# BW1092_Connector.net
KiCad netlist of a schematic drawn in Altium Designer
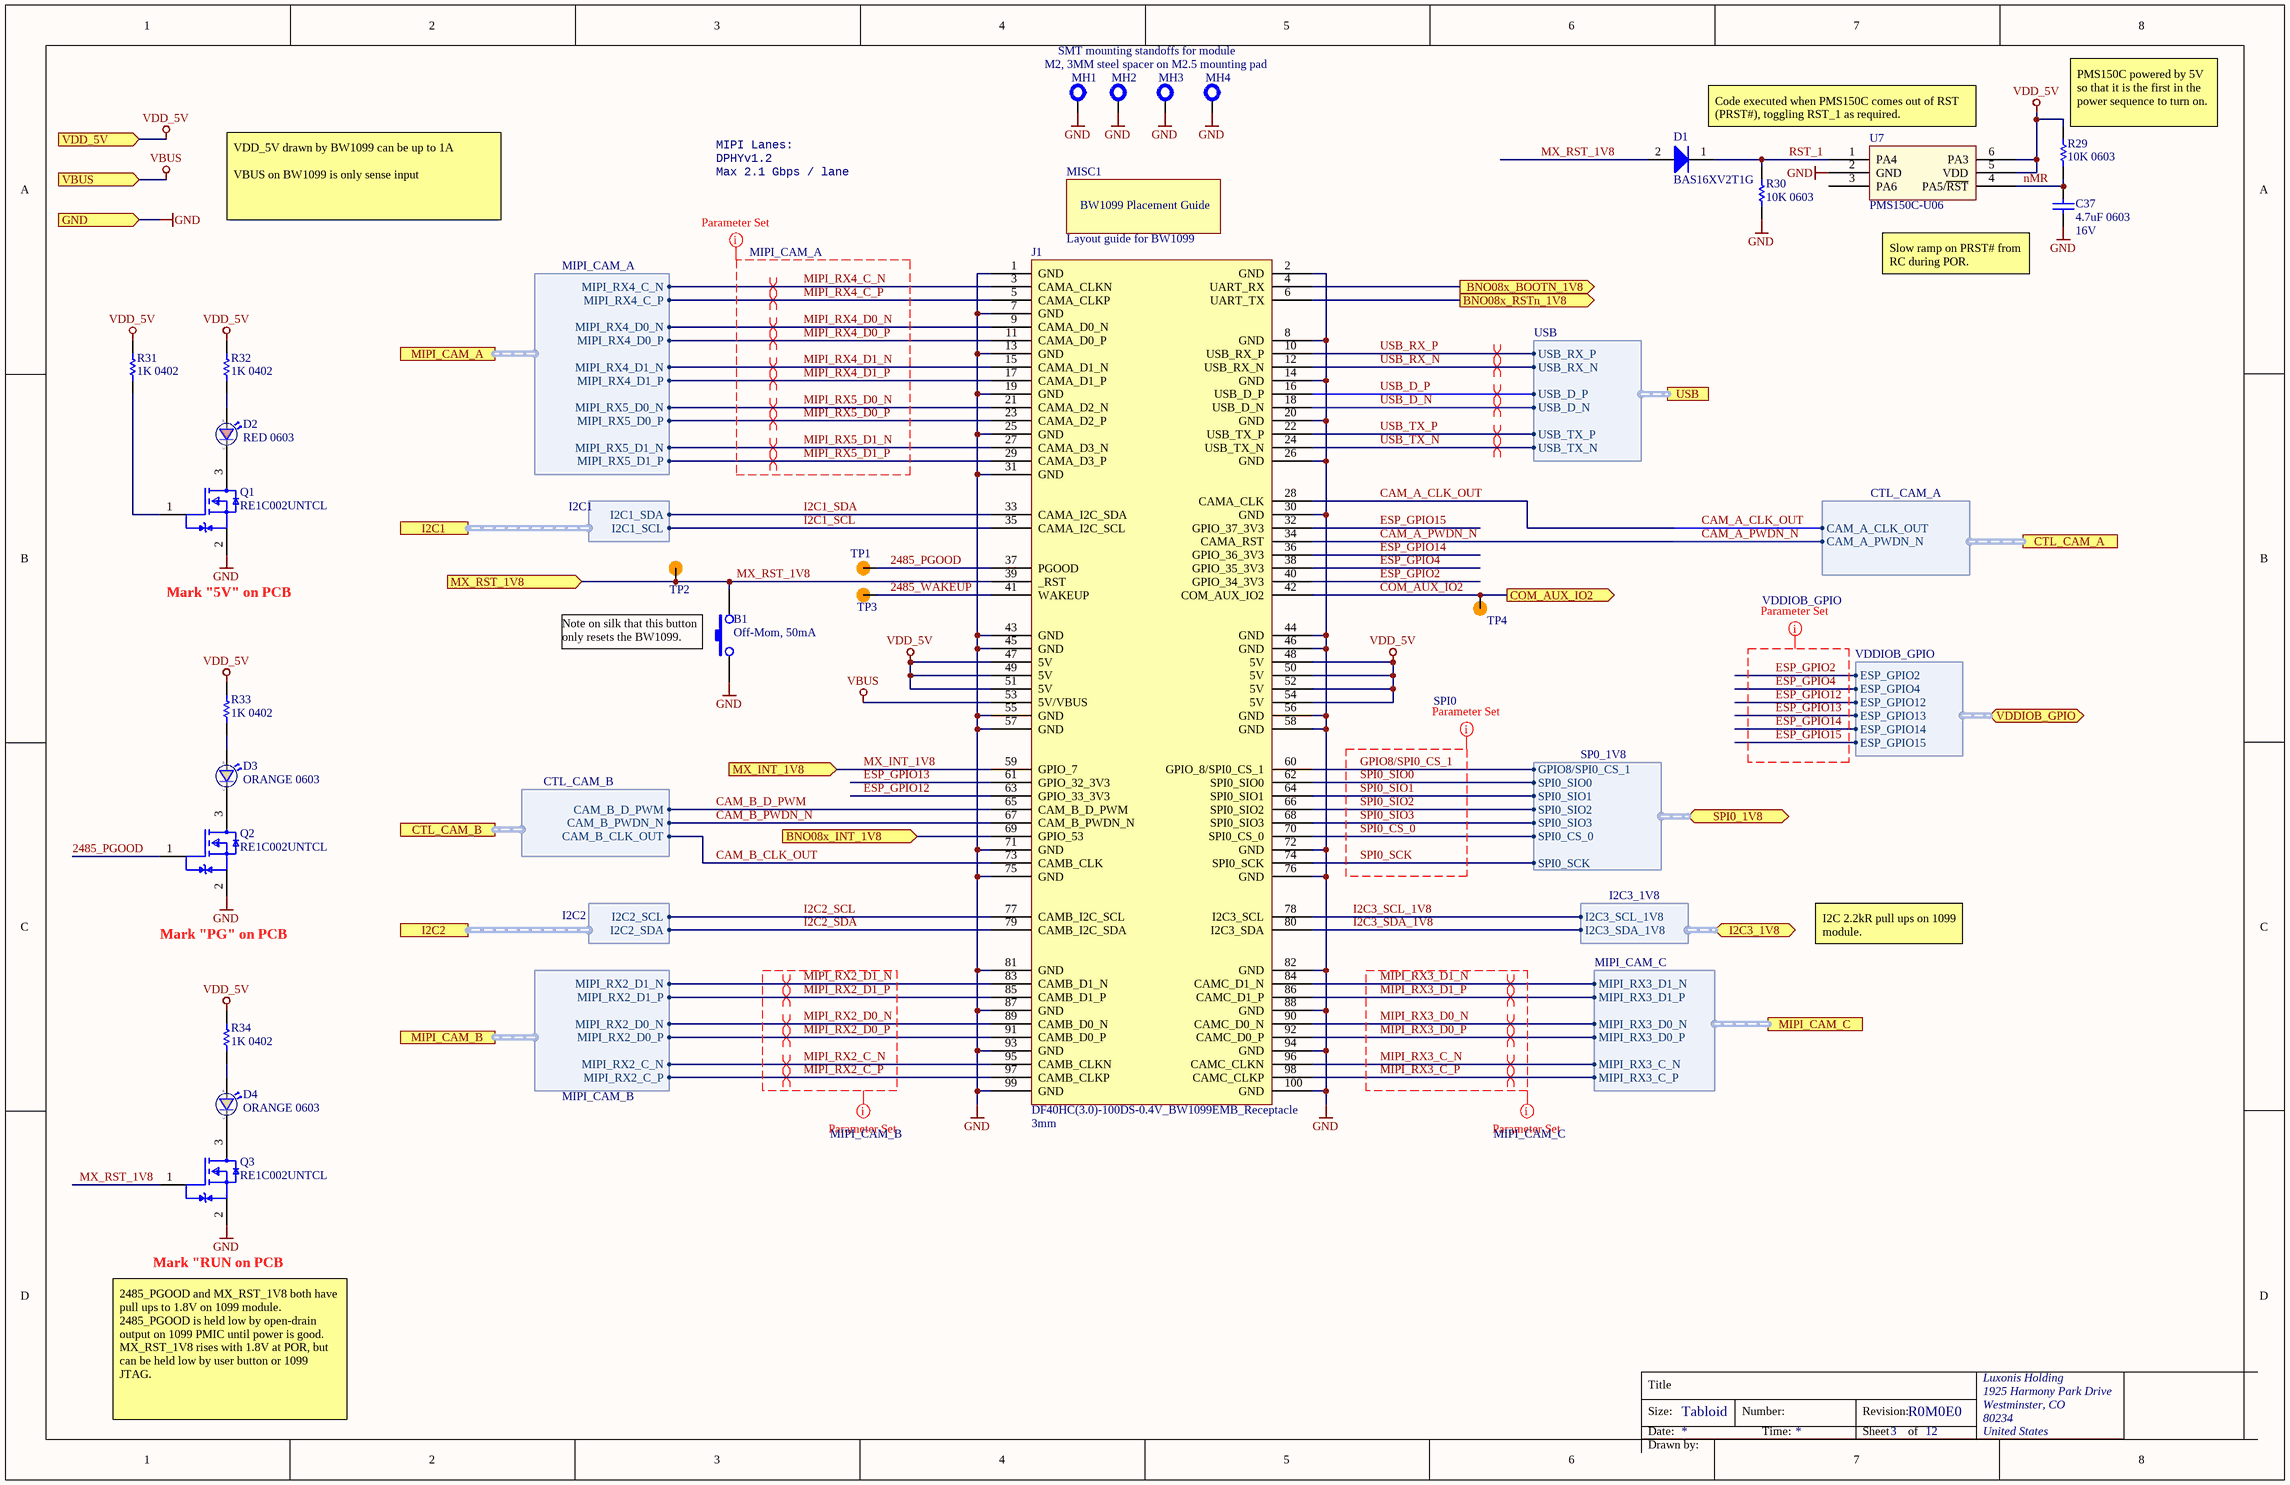
[diagram p0: BW1092_Connector.SchDoc]

(export (version "E")
  (design (tool "Eeschema 10.0.6"))
  (components
    (comp (ref "B1")
      (value "Off-Mom, 50mA")
      (footprint "LuxonisMaster:DTSM-32N-V")
      (description "SWITCH TACTILE SMT 3.5mm * 6mm , brown 160gf")
      (libsource (lib "LuxonisMaster") (part "DTSM-32N-V"))
    )
    (comp (ref "C37")
      (value "4.7uF 0603")
      (footprint "CAP_Altium_Vault_Generic:CAPC0603(1608)100_N")
      (description "CAP CER 4.7UF 16V X5R 0603 10%")
      (fields (field (name "TOLERANCE") "10%") (field (name "VOLTAGE RATING") "16V"))
      (libsource (lib "LuxonisMaster") (part "GRM188R61C475KAAJD"))
    )
    (comp (ref "D1")
      (value "BAS16XV2T1G")
      (footprint "LuxonisMaster:BAS16XV2T1G")
      (description "DIODE GEN PURP 75V 200MA SOD523")
      (libsource (lib "LuxonisMaster") (part "BAS16XV2T1G"))
    )
    (comp (ref "D2")
      (value "RED 0603")
      (footprint "LuxonisMaster:SML_D1xx8W")
      (description "LED RED DIFFUSED 0603 SMD Red 620nm LED Indication - Discrete 2.2V 0603 (1608 Metric)")
      (libsource (lib "LuxonisMaster") (part "SML-D12U8WT86"))
    )
    (comp (ref "D3")
      (value "ORANGE 0603")
      (footprint "LuxonisMaster:SML_D1xx8W")
      (description "LED ORANGE DIFFUSED 0603 SMD Orange 605nm LED Indication - Discrete 2.2V 0603 (1608 Metric)")
      (libsource (lib "LuxonisMaster") (part "SML-D12D8WT86"))
    )
    (comp (ref "D4")
      (value "ORANGE 0603")
      (footprint "LuxonisMaster:SML_D1xx8W")
      (description "LED ORANGE DIFFUSED 0603 SMD Orange 605nm LED Indication - Discrete 2.2V 0603 (1608 Metric)")
      (libsource (lib "LuxonisMaster") (part "SML-D12D8WT86"))
    )
    (comp (ref "J1")
      (value "DF40HC(3.0)-100DS-0.4V_BW1099EMB_Receptacle")
      (footprint "LuxonisMaster:DF40HC-3.0-100DS-0.4V_minpad")
      (description "CONN RCPT 100POS 0.4MM SMD GOLD EMB PINOUT")
      (fields (field (name "MATED STACKING HEIGHT") "3mm"))
      (libsource (lib "BW1098EMB_R0M0E0") (part "DF40HC(3.0)-100DS-0.4V_BW1099EMB"))
    )
    (comp (ref "MH1")
      (value "M2, 3MM steel spacer on M2.5 mounting pad")
      (footprint "LuxonisMaster:9774030243R")
      (description "MP ROUND STANDOFF M2X0.4 STEEL 3MM")
      (libsource (lib "LuxonisMaster") (part "9774030243R"))
    )
    (comp (ref "MH2")
      (value "M2, 3MM steel spacer on M2.5 mounting pad")
      (footprint "LuxonisMaster:9774030243R")
      (description "MP ROUND STANDOFF M2X0.4 STEEL 3MM")
      (libsource (lib "LuxonisMaster") (part "9774030243R"))
    )
    (comp (ref "MH3")
      (value "M2, 3MM steel spacer on M2.5 mounting pad")
      (footprint "LuxonisMaster:9774030243R")
      (description "MP ROUND STANDOFF M2X0.4 STEEL 3MM")
      (libsource (lib "LuxonisMaster") (part "9774030243R"))
    )
    (comp (ref "MH4")
      (value "M2, 3MM steel spacer on M2.5 mounting pad")
      (footprint "LuxonisMaster:9774030243R")
      (description "MP ROUND STANDOFF M2X0.4 STEEL 3MM")
      (libsource (lib "LuxonisMaster") (part "9774030243R"))
    )
    (comp (ref "MISC1")
      (value "Layout guide for BW1099")
      (footprint "BW1099_R3_KTHSNF_Footprint")
      (description "MISC - Use for aligning BW1099 mount")
      (libsource (lib "LuxonisMaster") (part "BW1099_Footprint"))
    )
    (comp (ref "Q1")
      (value "RE1C002UNTCL")
      (footprint "LuxonisMaster:RE1C002UNTCL")
      (description "MOSFET N-CH 20V 0.2A EMT3")
      (libsource (lib "LuxonisMaster") (part "RE1C002UNTCL"))
    )
    (comp (ref "Q2")
      (value "RE1C002UNTCL")
      (footprint "LuxonisMaster:RE1C002UNTCL")
      (description "MOSFET N-CH 20V 0.2A EMT3")
      (libsource (lib "LuxonisMaster") (part "RE1C002UNTCL"))
    )
    (comp (ref "Q3")
      (value "RE1C002UNTCL")
      (footprint "LuxonisMaster:RE1C002UNTCL")
      (description "MOSFET N-CH 20V 0.2A EMT3")
      (libsource (lib "LuxonisMaster") (part "RE1C002UNTCL"))
    )
    (comp (ref "R29")
      (value "10K 0603")
      (footprint "RES_Altium_Vault_Generic:RESC0603(1608)_N")
      (description "RES SMD 10K OHM 1% 1/10W 0603")
      (fields (field (name "TOLERANCE") "1%"))
      (libsource (lib "LuxonisMaster") (part "RC0603FR-0710KL"))
    )
    (comp (ref "R30")
      (value "10K 0603")
      (footprint "RES_Altium_Vault_Generic:RESC0603(1608)_N")
      (description "RES SMD 10K OHM 1% 1/10W 0603")
      (fields (field (name "TOLERANCE") "1%"))
      (libsource (lib "LuxonisMaster") (part "RC0603FR-0710KL"))
    )
    (comp (ref "R31")
      (value "1K 0402")
      (footprint "RES_Altium_Vault_Generic:RESC0402(1005)_L")
      (fields (field (name "TOLERANCE") "1%"))
      (libsource (lib "LuxonisMaster") (part "RC0402FR-071KL"))
    )
    (comp (ref "R32")
      (value "1K 0402")
      (footprint "RES_Altium_Vault_Generic:RESC0402(1005)_L")
      (fields (field (name "TOLERANCE") "1%"))
      (libsource (lib "LuxonisMaster") (part "RC0402FR-071KL"))
    )
    (comp (ref "R33")
      (value "1K 0402")
      (footprint "RES_Altium_Vault_Generic:RESC0402(1005)_L")
      (fields (field (name "TOLERANCE") "1%"))
      (libsource (lib "LuxonisMaster") (part "RC0402FR-071KL"))
    )
    (comp (ref "R34")
      (value "1K 0402")
      (footprint "RES_Altium_Vault_Generic:RESC0402(1005)_L")
      (fields (field (name "TOLERANCE") "1%"))
      (libsource (lib "LuxonisMaster") (part "RC0402FR-071KL"))
    )
    (comp (ref "TP1")
      (value "TP100_200_NS")
      (footprint "LuxonisMaster:TP100_200_NS")
      (libsource (lib "LuxonisMaster") (part "TEST_POINT"))
    )
    (comp (ref "TP2")
      (value "TP100_200_NS")
      (footprint "LuxonisMaster:TP100_200_NS")
      (libsource (lib "LuxonisMaster") (part "TEST_POINT"))
    )
    (comp (ref "TP3")
      (value "TP100_200_NS")
      (footprint "LuxonisMaster:TP100_200_NS")
      (libsource (lib "LuxonisMaster") (part "TEST_POINT"))
    )
    (comp (ref "TP4")
      (value "TP100_200_NS")
      (footprint "LuxonisMaster:TP100_200_NS")
      (libsource (lib "LuxonisMaster") (part "TEST_POINT"))
    )
    (comp (ref "U7")
      (value "PMS150C-U06")
      (footprint "LuxonisMaster:PMS150C-U06")
      (description "Padauk 8bit OTP Type IO Controller - (SOT-23-6)")
      (libsource (lib "LuxonisMaster") (part "PMS150C-U06"))
    )
  )
  (nets
    (net (code "12") (name "/2485_PGOOD") (class "Default")
      (node (ref "J1") (pin "37") (pinfunction "PGOOD_37") (pintype "passive"))
      (node (ref "Q2") (pin "1") (pinfunction "Gate_1") (pintype "passive"))
      (node (ref "TP1") (pin "1") (pintype "passive"))
    )
    (net (code "13") (name "/2485_WAKEUP") (class "Default")
      (node (ref "J1") (pin "41") (pinfunction "WAKEUP_41") (pintype "passive"))
      (node (ref "TP3") (pin "1") (pintype "passive"))
    )
    (net (code "14") (name "/BNO08x_BOOTN_1V8") (class "Default")
      (node (ref "J1") (pin "4") (pinfunction "UART_RX_4") (pintype "passive"))
    )
    (net (code "15") (name "/BNO08x_INT_1V8") (class "Default")
      (node (ref "J1") (pin "69") (pinfunction "GPIO_53_69") (pintype "passive"))
    )
    (net (code "16") (name "/BNO08x_RSTn_1V8") (class "Default")
      (node (ref "J1") (pin "6") (pinfunction "UART_TX_6") (pintype "passive"))
    )
    (net (code "17") (name "/CAM_A_CLK_OUT") (class "Default")
      (node (ref "J1") (pin "28") (pinfunction "CAMA_CLK_28") (pintype "passive"))
    )
    (net (code "18") (name "/CAM_A_PWDN_N") (class "Default")
      (node (ref "J1") (pin "34") (pinfunction "CAMA_RST_34") (pintype "passive"))
    )
    (net (code "19") (name "/CAM_B_CLK_OUT") (class "Default")
      (node (ref "J1") (pin "73") (pinfunction "CAMB_CLK_73") (pintype "passive"))
    )
    (net (code "20") (name "/CAM_B_D_PWM") (class "Default")
      (node (ref "J1") (pin "65") (pinfunction "CAM_B_D_PWM_65") (pintype "passive"))
    )
    (net (code "21") (name "/CAM_B_PWDN_N") (class "Default")
      (node (ref "J1") (pin "67") (pinfunction "CAM_B_PWDN_N_67") (pintype "passive"))
    )
    (net (code "22") (name "/COM_AUX_IO2") (class "Default")
      (node (ref "J1") (pin "42") (pinfunction "COM_AUX_IO2_42") (pintype "passive"))
      (node (ref "TP4") (pin "1") (pintype "passive"))
    )
    (net (code "23") (name "/ESP_GPIO2") (class "Default")
      (node (ref "J1") (pin "40") (pinfunction "GPIO_34_3V3_40") (pintype "passive"))
    )
    (net (code "24") (name "/ESP_GPIO4") (class "Default")
      (node (ref "J1") (pin "38") (pinfunction "GPIO_35_3V3_38") (pintype "passive"))
    )
    (net (code "25") (name "/ESP_GPIO12") (class "Default")
      (node (ref "J1") (pin "63") (pinfunction "GPIO_33_3V3_63") (pintype "passive"))
    )
    (net (code "26") (name "/ESP_GPIO13") (class "Default")
      (node (ref "J1") (pin "61") (pinfunction "GPIO_32_3V3_61") (pintype "passive"))
    )
    (net (code "27") (name "/ESP_GPIO14") (class "Default")
      (node (ref "J1") (pin "36") (pinfunction "GPIO_36_3V3_36") (pintype "passive"))
    )
    (net (code "28") (name "/ESP_GPIO15") (class "Default")
      (node (ref "J1") (pin "32") (pinfunction "GPIO_37_3V3_32") (pintype "passive"))
    )
    (net (code "29") (name "/GPIO8{slash}SPI0_CS_1") (class "Default")
      (node (ref "J1") (pin "60") (pinfunction "GPIO_8/SPI0_CS_1_60") (pintype "passive"))
    )
    (net (code "30") (name "/I2C1_SCL") (class "Default")
      (node (ref "J1") (pin "35") (pinfunction "CAMA_I2C_SCL_35") (pintype "passive"))
    )
    (net (code "31") (name "/I2C1_SDA") (class "Default")
      (node (ref "J1") (pin "33") (pinfunction "CAMA_I2C_SDA_33") (pintype "passive"))
    )
    (net (code "32") (name "/I2C2_SCL") (class "Default")
      (node (ref "J1") (pin "77") (pinfunction "CAMB_I2C_SCL_77") (pintype "passive"))
    )
    (net (code "33") (name "/I2C2_SDA") (class "Default")
      (node (ref "J1") (pin "79") (pinfunction "CAMB_I2C_SDA_79") (pintype "passive"))
    )
    (net (code "34") (name "/I2C3_SCL_1V8") (class "Default")
      (node (ref "J1") (pin "78") (pinfunction "I2C3_SCL_78") (pintype "passive"))
    )
    (net (code "35") (name "/I2C3_SDA_1V8") (class "Default")
      (node (ref "J1") (pin "80") (pinfunction "I2C3_SDA_80") (pintype "passive"))
    )
    (net (code "36") (name "/MIPI_RX2_C_N") (class "Default")
      (node (ref "J1") (pin "95") (pinfunction "CAMB_CLKN_95") (pintype "passive"))
    )
    (net (code "37") (name "/MIPI_RX2_C_P") (class "Default")
      (node (ref "J1") (pin "97") (pinfunction "CAMB_CLKP_97") (pintype "passive"))
    )
    (net (code "38") (name "/MIPI_RX2_D0_N") (class "Default")
      (node (ref "J1") (pin "89") (pinfunction "CAMB_D0_N_89") (pintype "passive"))
    )
    (net (code "39") (name "/MIPI_RX2_D0_P") (class "Default")
      (node (ref "J1") (pin "91") (pinfunction "CAMB_D0_P_91") (pintype "passive"))
    )
    (net (code "40") (name "/MIPI_RX2_D1_N") (class "Default")
      (node (ref "J1") (pin "83") (pinfunction "CAMB_D1_N_83") (pintype "passive"))
    )
    (net (code "41") (name "/MIPI_RX2_D1_P") (class "Default")
      (node (ref "J1") (pin "85") (pinfunction "CAMB_D1_P_85") (pintype "passive"))
    )
    (net (code "42") (name "/MIPI_RX3_C_N") (class "Default")
      (node (ref "J1") (pin "96") (pinfunction "CAMC_CLKN_96") (pintype "passive"))
    )
    (net (code "43") (name "/MIPI_RX3_C_P") (class "Default")
      (node (ref "J1") (pin "98") (pinfunction "CAMC_CLKP_98") (pintype "passive"))
    )
    (net (code "44") (name "/MIPI_RX3_D0_N") (class "Default")
      (node (ref "J1") (pin "90") (pinfunction "CAMC_D0_N_90") (pintype "passive"))
    )
    (net (code "45") (name "/MIPI_RX3_D0_P") (class "Default")
      (node (ref "J1") (pin "92") (pinfunction "CAMC_D0_P_92") (pintype "passive"))
    )
    (net (code "46") (name "/MIPI_RX3_D1_N") (class "Default")
      (node (ref "J1") (pin "84") (pinfunction "CAMC_D1_N_84") (pintype "passive"))
    )
    (net (code "47") (name "/MIPI_RX3_D1_P") (class "Default")
      (node (ref "J1") (pin "86") (pinfunction "CAMC_D1_P_86") (pintype "passive"))
    )
    (net (code "48") (name "/MIPI_RX4_C_N") (class "Default")
      (node (ref "J1") (pin "3") (pinfunction "CAMA_CLKN_3") (pintype "passive"))
    )
    (net (code "49") (name "/MIPI_RX4_C_P") (class "Default")
      (node (ref "J1") (pin "5") (pinfunction "CAMA_CLKP_5") (pintype "passive"))
    )
    (net (code "50") (name "/MIPI_RX4_D0_N") (class "Default")
      (node (ref "J1") (pin "9") (pinfunction "CAMA_D0_N_9") (pintype "passive"))
    )
    (net (code "51") (name "/MIPI_RX4_D0_P") (class "Default")
      (node (ref "J1") (pin "11") (pinfunction "CAMA_D0_P_11") (pintype "passive"))
    )
    (net (code "52") (name "/MIPI_RX4_D1_N") (class "Default")
      (node (ref "J1") (pin "15") (pinfunction "CAMA_D1_N_15") (pintype "passive"))
    )
    (net (code "53") (name "/MIPI_RX4_D1_P") (class "Default")
      (node (ref "J1") (pin "17") (pinfunction "CAMA_D1_P_17") (pintype "passive"))
    )
    (net (code "54") (name "/MIPI_RX5_D0_N") (class "Default")
      (node (ref "J1") (pin "21") (pinfunction "CAMA_D2_N_21") (pintype "passive"))
    )
    (net (code "55") (name "/MIPI_RX5_D0_P") (class "Default")
      (node (ref "J1") (pin "23") (pinfunction "CAMA_D2_P_23") (pintype "passive"))
    )
    (net (code "56") (name "/MIPI_RX5_D1_N") (class "Default")
      (node (ref "J1") (pin "27") (pinfunction "CAMA_D3_N_27") (pintype "passive"))
    )
    (net (code "57") (name "/MIPI_RX5_D1_P") (class "Default")
      (node (ref "J1") (pin "29") (pinfunction "CAMA_D3_P_29") (pintype "passive"))
    )
    (net (code "58") (name "/MX_INT_1V8") (class "Default")
      (node (ref "J1") (pin "59") (pinfunction "GPIO_7_59") (pintype "passive"))
    )
    (net (code "59") (name "/MX_RST_1V8") (class "Default")
      (node (ref "B1") (pin "2") (pinfunction "2_2") (pintype "passive"))
      (node (ref "D1") (pin "2") (pinfunction "A_2") (pintype "passive"))
      (node (ref "J1") (pin "39") (pinfunction "_RST_39") (pintype "passive"))
      (node (ref "Q3") (pin "1") (pinfunction "Gate_1") (pintype "passive"))
      (node (ref "TP2") (pin "1") (pintype "passive"))
    )
    (net (code "60") (name "/RST_1") (class "Default")
      (node (ref "D1") (pin "1") (pinfunction "K_1") (pintype "passive"))
      (node (ref "R30") (pin "2") (pinfunction "2_2") (pintype "passive"))
      (node (ref "U7") (pin "1") (pinfunction "PA4_1") (pintype "passive"))
    )
    (net (code "61") (name "/SPI0_CS_0") (class "Default")
      (node (ref "J1") (pin "70") (pinfunction "SPI0_CS_0_70") (pintype "passive"))
    )
    (net (code "62") (name "/SPI0_SCK") (class "Default")
      (node (ref "J1") (pin "74") (pinfunction "SPI0_SCK_74") (pintype "passive"))
    )
    (net (code "63") (name "/SPI0_SIO0") (class "Default")
      (node (ref "J1") (pin "62") (pinfunction "SPI0_SIO0_62") (pintype "passive"))
    )
    (net (code "64") (name "/SPI0_SIO1") (class "Default")
      (node (ref "J1") (pin "64") (pinfunction "SPI0_SIO1_64") (pintype "passive"))
    )
    (net (code "65") (name "/SPI0_SIO2") (class "Default")
      (node (ref "J1") (pin "66") (pinfunction "SPI0_SIO2_66") (pintype "passive"))
    )
    (net (code "66") (name "/SPI0_SIO3") (class "Default")
      (node (ref "J1") (pin "68") (pinfunction "SPI0_SIO3_68") (pintype "passive"))
    )
    (net (code "67") (name "/USB_D_N") (class "Default")
      (node (ref "J1") (pin "18") (pinfunction "USB_D_N_18") (pintype "passive"))
    )
    (net (code "68") (name "/USB_D_P") (class "Default")
      (node (ref "J1") (pin "16") (pinfunction "USB_D_P_16") (pintype "passive"))
    )
    (net (code "69") (name "/USB_RX_N") (class "Default")
      (node (ref "J1") (pin "12") (pinfunction "USB_RX_N_12") (pintype "passive"))
    )
    (net (code "70") (name "/USB_RX_P") (class "Default")
      (node (ref "J1") (pin "10") (pinfunction "USB_RX_P_10") (pintype "passive"))
    )
    (net (code "71") (name "/USB_TX_N") (class "Default")
      (node (ref "J1") (pin "24") (pinfunction "USB_TX_N_24") (pintype "passive"))
    )
    (net (code "72") (name "/USB_TX_P") (class "Default")
      (node (ref "J1") (pin "22") (pinfunction "USB_TX_P_22") (pintype "passive"))
    )
    (net (code "73") (name "/nMR") (class "Default")
      (node (ref "C37") (pin "2") (pinfunction "2_2") (pintype "passive"))
      (node (ref "R29") (pin "1") (pinfunction "1_1") (pintype "passive"))
      (node (ref "U7") (pin "4") (pinfunction "PA5/~{RST}_4") (pintype "passive"))
    )
    (net (code "85") (name "GND") (class "Default")
      (node (ref "B1") (pin "1") (pinfunction "1_1") (pintype "passive"))
      (node (ref "C37") (pin "1") (pinfunction "1_1") (pintype "passive"))
      (node (ref "J1") (pin "1") (pinfunction "GND_1") (pintype "passive"))
      (node (ref "J1") (pin "100") (pinfunction "GND_100") (pintype "passive"))
      (node (ref "J1") (pin "13") (pinfunction "GND_13") (pintype "passive"))
      (node (ref "J1") (pin "14") (pinfunction "GND_14") (pintype "passive"))
      (node (ref "J1") (pin "19") (pinfunction "GND_19") (pintype "passive"))
      (node (ref "J1") (pin "2") (pinfunction "GND_2") (pintype "passive"))
      (node (ref "J1") (pin "20") (pinfunction "GND_20") (pintype "passive"))
      (node (ref "J1") (pin "25") (pinfunction "GND_25") (pintype "passive"))
      (node (ref "J1") (pin "26") (pinfunction "GND_26") (pintype "passive"))
      (node (ref "J1") (pin "30") (pinfunction "GND_30") (pintype "passive"))
      (node (ref "J1") (pin "31") (pinfunction "GND_31") (pintype "passive"))
      (node (ref "J1") (pin "43") (pinfunction "GND_43") (pintype "passive"))
      (node (ref "J1") (pin "44") (pinfunction "GND_44") (pintype "passive"))
      (node (ref "J1") (pin "45") (pinfunction "GND_45") (pintype "passive"))
      (node (ref "J1") (pin "46") (pinfunction "GND_46") (pintype "passive"))
      (node (ref "J1") (pin "55") (pinfunction "GND_55") (pintype "passive"))
      (node (ref "J1") (pin "56") (pinfunction "GND_56") (pintype "passive"))
      (node (ref "J1") (pin "57") (pinfunction "GND_57") (pintype "passive"))
      (node (ref "J1") (pin "58") (pinfunction "GND_58") (pintype "passive"))
      (node (ref "J1") (pin "7") (pinfunction "GND_7") (pintype "passive"))
      (node (ref "J1") (pin "71") (pinfunction "GND_71") (pintype "passive"))
      (node (ref "J1") (pin "72") (pinfunction "GND_72") (pintype "passive"))
      (node (ref "J1") (pin "75") (pinfunction "GND_75") (pintype "passive"))
      (node (ref "J1") (pin "76") (pinfunction "GND_76") (pintype "passive"))
      (node (ref "J1") (pin "8") (pinfunction "GND_8") (pintype "passive"))
      (node (ref "J1") (pin "81") (pinfunction "GND_81") (pintype "passive"))
      (node (ref "J1") (pin "82") (pinfunction "GND_82") (pintype "passive"))
      (node (ref "J1") (pin "87") (pinfunction "GND_87") (pintype "passive"))
      (node (ref "J1") (pin "88") (pinfunction "GND_88") (pintype "passive"))
      (node (ref "J1") (pin "93") (pinfunction "GND_93") (pintype "passive"))
      (node (ref "J1") (pin "94") (pinfunction "GND_94") (pintype "passive"))
      (node (ref "J1") (pin "99") (pinfunction "GND_99") (pintype "passive"))
      (node (ref "MH1") (pin "1") (pintype "passive"))
      (node (ref "MH2") (pin "1") (pintype "passive"))
      (node (ref "MH3") (pin "1") (pintype "passive"))
      (node (ref "MH4") (pin "1") (pintype "passive"))
      (node (ref "Q1") (pin "2") (pinfunction "Source_2") (pintype "passive"))
      (node (ref "Q2") (pin "2") (pinfunction "Source_2") (pintype "passive"))
      (node (ref "Q3") (pin "2") (pinfunction "Source_2") (pintype "passive"))
      (node (ref "R30") (pin "1") (pinfunction "1_1") (pintype "passive"))
      (node (ref "U7") (pin "2") (pinfunction "GND_2") (pintype "passive"))
    )
    (net (code "86") (name "Net-(D2-A)") (class "Default")
      (node (ref "D2") (pin "2") (pinfunction "A_2") (pintype "passive"))
      (node (ref "R32") (pin "1") (pinfunction "1_1") (pintype "passive"))
    )
    (net (code "87") (name "Net-(D2-C)") (class "Default")
      (node (ref "D2") (pin "1") (pinfunction "C_1") (pintype "passive"))
      (node (ref "Q1") (pin "3") (pinfunction "Drain_3") (pintype "passive"))
    )
    (net (code "88") (name "Net-(D3-A)") (class "Default")
      (node (ref "D3") (pin "2") (pinfunction "A_2") (pintype "passive"))
      (node (ref "R33") (pin "1") (pinfunction "1_1") (pintype "passive"))
    )
    (net (code "89") (name "Net-(D3-C)") (class "Default")
      (node (ref "D3") (pin "1") (pinfunction "C_1") (pintype "passive"))
      (node (ref "Q2") (pin "3") (pinfunction "Drain_3") (pintype "passive"))
    )
    (net (code "90") (name "Net-(D4-A)") (class "Default")
      (node (ref "D4") (pin "2") (pinfunction "A_2") (pintype "passive"))
      (node (ref "R34") (pin "1") (pinfunction "1_1") (pintype "passive"))
    )
    (net (code "91") (name "Net-(D4-C)") (class "Default")
      (node (ref "D4") (pin "1") (pinfunction "C_1") (pintype "passive"))
      (node (ref "Q3") (pin "3") (pinfunction "Drain_3") (pintype "passive"))
    )
    (net (code "92") (name "Net-(Q1-Gate)") (class "Default")
      (node (ref "Q1") (pin "1") (pinfunction "Gate_1") (pintype "passive"))
      (node (ref "R31") (pin "1") (pinfunction "1_1") (pintype "passive"))
    )
    (net (code "93") (name "VBUS") (class "Default")
      (node (ref "J1") (pin "53") (pinfunction "5V/VBUS_53") (pintype "passive"))
    )
    (net (code "94") (name "VDD_5V") (class "Default")
      (node (ref "J1") (pin "47") (pinfunction "5V_47") (pintype "passive"))
      (node (ref "J1") (pin "48") (pinfunction "5V_48") (pintype "passive"))
      (node (ref "J1") (pin "49") (pinfunction "5V_49") (pintype "passive"))
      (node (ref "J1") (pin "50") (pinfunction "5V_50") (pintype "passive"))
      (node (ref "J1") (pin "51") (pinfunction "5V_51") (pintype "passive"))
      (node (ref "J1") (pin "52") (pinfunction "5V_52") (pintype "passive"))
      (node (ref "J1") (pin "54") (pinfunction "5V_54") (pintype "passive"))
      (node (ref "R29") (pin "2") (pinfunction "2_2") (pintype "passive"))
      (node (ref "R31") (pin "2") (pinfunction "2_2") (pintype "passive"))
      (node (ref "R32") (pin "2") (pinfunction "2_2") (pintype "passive"))
      (node (ref "R33") (pin "2") (pinfunction "2_2") (pintype "passive"))
      (node (ref "R34") (pin "2") (pinfunction "2_2") (pintype "passive"))
      (node (ref "U7") (pin "5") (pinfunction "VDD_5") (pintype "passive"))
      (node (ref "U7") (pin "6") (pinfunction "PA3_6") (pintype "passive"))
    )
    (net (code "95") (name "unconnected-(U7-PA6-Pad3)") (class "Default")
      (node (ref "U7") (pin "3") (pinfunction "PA6_3") (pintype "passive"))
    )
  )
)
